# PCB_Arduino1.net
KiCad netlist of a schematic drawn in EAGLE
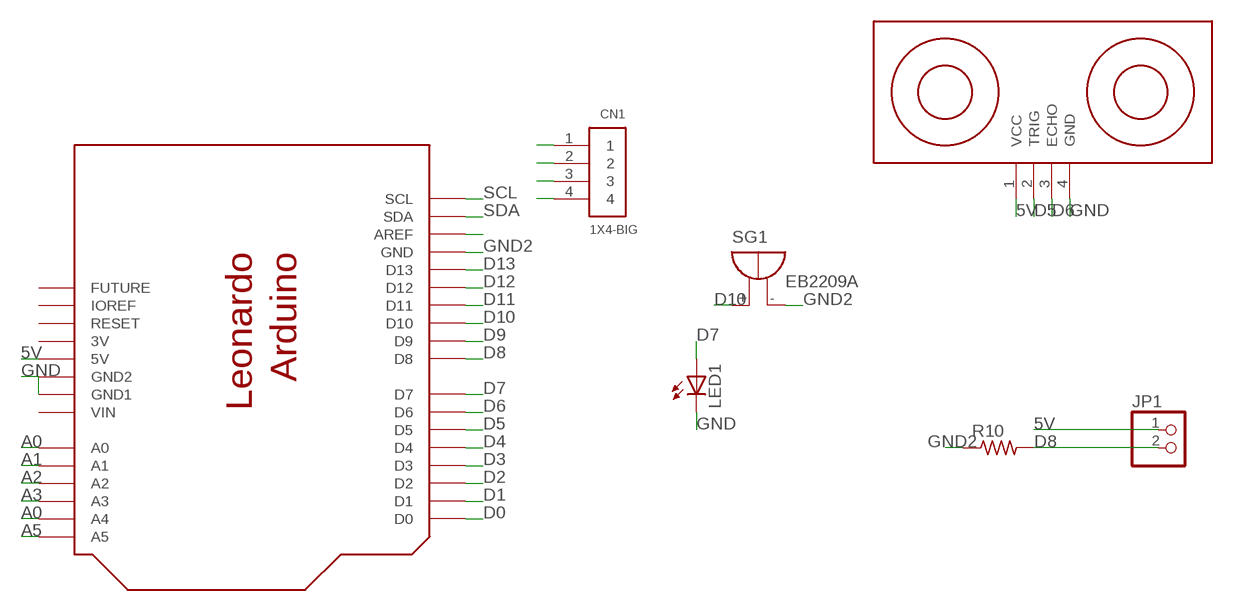
[diagram p0: schematic, sheet 1]

(export (version "E")
  (design (tool "Eeschema 10.0.6"))
  (components
    (comp (ref "CN1")
      (value "1X4-BIG")
      (footprint "eagle-import:1X04-BIG")
      (libsource (lib "eagle-import") (part "1X4-BIG"))
    )
    (comp (ref "JP1")
      (value "PINHD-1X2")
      (footprint "eagle-import:1X02")
      (libsource (lib "eagle-import") (part "PINHD-1X2"))
    )
    (comp (ref "LED1")
      (value "LEDB152")
      (footprint "eagle-import:Q62902-B152")
      (libsource (lib "eagle-import") (part "LEDB152"))
    )
    (comp (ref "R10")
      (value "R-US_0204/7")
      (footprint "eagle-import:0204_7")
      (libsource (lib "eagle-import") (part "R-US_0204/7"))
    )
    (comp (ref "SG1")
      (value "EB2209A")
      (footprint "eagle-import:EB2209A")
      (libsource (lib "eagle-import") (part "EB2209A"))
    )
    (comp (ref "U$1")
      (value "ARDUINO_LEONARDO")
      (footprint "eagle-import:ARDUINO_LEONARDO")
      (libsource (lib "eagle-import") (part "ARDUINO_LEONARDO"))
    )
    (comp (ref "U$2")
      (value "ULTRASONIC-HC-SR04")
      (footprint "eagle-import:ULTRASONIC-HC-SR04")
      (libsource (lib "eagle-import") (part "ULTRASONIC-HC-SR04"))
    )
  )
  (nets
    (net (code "1") (name "/3V") (class "Default")
      (node (ref "U$1") (pin "3V") (pinfunction "3V_3V") (pintype "power_in"))
    )
    (net (code "2") (name "/5V") (class "Default")
      (node (ref "CN1") (pin "1") (pinfunction "1_1") (pintype "bidirectional"))
      (node (ref "JP1") (pin "1") (pinfunction "1_1") (pintype "passive"))
      (node (ref "U$1") (pin "5V") (pinfunction "5V_5V") (pintype "power_in"))
      (node (ref "U$2") (pin "1") (pinfunction "VCC_1") (pintype "power_in"))
    )
    (net (code "3") (name "/A0") (class "Default")
      (node (ref "U$1") (pin "A0") (pinfunction "A0_A0") (pintype "bidirectional"))
    )
    (net (code "4") (name "/A1") (class "Default")
      (node (ref "U$1") (pin "A1") (pinfunction "A1_A1") (pintype "bidirectional"))
    )
    (net (code "5") (name "/A2") (class "Default")
      (node (ref "U$1") (pin "A2") (pinfunction "A2_A2") (pintype "bidirectional"))
    )
    (net (code "6") (name "/A3") (class "Default")
      (node (ref "U$1") (pin "A3") (pinfunction "A3_A3") (pintype "bidirectional"))
    )
    (net (code "7") (name "/A5") (class "Default")
      (node (ref "U$1") (pin "A5") (pinfunction "A5_A5") (pintype "bidirectional"))
    )
    (net (code "8") (name "/D0") (class "Default")
      (node (ref "U$1") (pin "D0") (pinfunction "D0_D0") (pintype "bidirectional"))
    )
    (net (code "9") (name "/D1") (class "Default")
      (node (ref "U$1") (pin "D1") (pinfunction "D1_D1") (pintype "bidirectional"))
    )
    (net (code "10") (name "/D2") (class "Default")
      (node (ref "U$1") (pin "D2") (pinfunction "D2_D2") (pintype "bidirectional"))
    )
    (net (code "11") (name "/D3") (class "Default")
      (node (ref "U$1") (pin "D3") (pinfunction "D3_D3") (pintype "bidirectional"))
    )
    (net (code "12") (name "/D4") (class "Default")
      (node (ref "U$1") (pin "D4") (pinfunction "D4_D4") (pintype "bidirectional"))
    )
    (net (code "13") (name "/D5") (class "Default")
      (node (ref "U$1") (pin "D5") (pinfunction "D5_D5") (pintype "bidirectional"))
      (node (ref "U$2") (pin "2") (pinfunction "TRIG_2") (pintype "input"))
    )
    (net (code "14") (name "/D6") (class "Default")
      (node (ref "U$1") (pin "D6") (pinfunction "D6_D6") (pintype "bidirectional"))
      (node (ref "U$2") (pin "3") (pinfunction "ECHO_3") (pintype "output"))
    )
    (net (code "15") (name "/D7") (class "Default")
      (node (ref "LED1") (pin "A") (pinfunction "A_A") (pintype "passive"))
      (node (ref "U$1") (pin "D7") (pinfunction "D7_D7") (pintype "bidirectional"))
    )
    (net (code "16") (name "/D8") (class "Default")
      (node (ref "JP1") (pin "2") (pinfunction "2_2") (pintype "passive"))
      (node (ref "R10") (pin "2") (pinfunction "2_2") (pintype "passive"))
      (node (ref "U$1") (pin "D8") (pinfunction "D8_D8") (pintype "bidirectional"))
    )
    (net (code "17") (name "/D9") (class "Default")
      (node (ref "U$1") (pin "D9") (pinfunction "D9_D9") (pintype "bidirectional"))
    )
    (net (code "18") (name "/D10") (class "Default")
      (node (ref "SG1") (pin "+") (pinfunction "+_+") (pintype "passive"))
      (node (ref "U$1") (pin "D10") (pinfunction "D10_D10") (pintype "bidirectional"))
    )
    (net (code "19") (name "/D11") (class "Default")
      (node (ref "U$1") (pin "D11") (pinfunction "D11_D11") (pintype "bidirectional"))
    )
    (net (code "20") (name "/D12") (class "Default")
      (node (ref "U$1") (pin "D12") (pinfunction "D12_D12") (pintype "bidirectional"))
    )
    (net (code "21") (name "/D13") (class "Default")
      (node (ref "U$1") (pin "D13") (pinfunction "D13_D13") (pintype "bidirectional"))
    )
    (net (code "22") (name "/GND") (class "Default")
      (node (ref "CN1") (pin "2") (pinfunction "2_2") (pintype "bidirectional"))
      (node (ref "LED1") (pin "K") (pinfunction "C_K") (pintype "passive"))
      (node (ref "U$1") (pin "GND$2") (pinfunction "GND2_GND$2") (pintype "power_in"))
      (node (ref "U$1") (pin "GND$3") (pinfunction "GND1_GND$3") (pintype "power_in"))
      (node (ref "U$2") (pin "4") (pinfunction "GND_4") (pintype "power_in"))
    )
    (net (code "23") (name "/GND2") (class "Default")
      (node (ref "R10") (pin "1") (pinfunction "1_1") (pintype "passive"))
      (node (ref "SG1") (pin "-") (pinfunction "-_-") (pintype "passive"))
      (node (ref "U$1") (pin "GND") (pinfunction "GND_GND") (pintype "power_in"))
    )
    (net (code "24") (name "/SCL") (class "Default")
      (node (ref "CN1") (pin "4") (pinfunction "4_4") (pintype "bidirectional"))
      (node (ref "U$1") (pin "SCL") (pinfunction "SCL_SCL") (pintype "bidirectional"))
    )
    (net (code "25") (name "/SDA") (class "Default")
      (node (ref "CN1") (pin "3") (pinfunction "3_3") (pintype "bidirectional"))
      (node (ref "U$1") (pin "SDA") (pinfunction "SDA_SDA") (pintype "bidirectional"))
    )
    (net (code "26") (name "/VIN") (class "Default")
      (node (ref "U$1") (pin "VIN") (pinfunction "VIN_VIN") (pintype "power_in"))
    )
    (net (code "27") (name "unconnected-(U$1-FUTURE-PadRESERVED)") (class "Default")
      (node (ref "U$1") (pin "RESERVED") (pinfunction "FUTURE_RESERVED") (pintype "bidirectional"))
    )
    (net (code "28") (name "unconnected-(U$1-PadA4)") (class "Default")
      (node (ref "U$1") (pin "A4") (pinfunction "A4_A4") (pintype "bidirectional"))
    )
    (net (code "29") (name "unconnected-(U$1-PadAREF)") (class "Default")
      (node (ref "U$1") (pin "AREF") (pinfunction "AREF_AREF") (pintype "bidirectional"))
    )
    (net (code "30") (name "unconnected-(U$1-PadIOREF)") (class "Default")
      (node (ref "U$1") (pin "IOREF") (pinfunction "IOREF_IOREF") (pintype "bidirectional"))
    )
    (net (code "31") (name "unconnected-(U$1-PadRESET)") (class "Default")
      (node (ref "U$1") (pin "RESET") (pinfunction "RESET_RESET") (pintype "bidirectional"))
    )
  )
)
